# arduino_ir_receiver.net
KiCad netlist of a schematic drawn in EAGLE
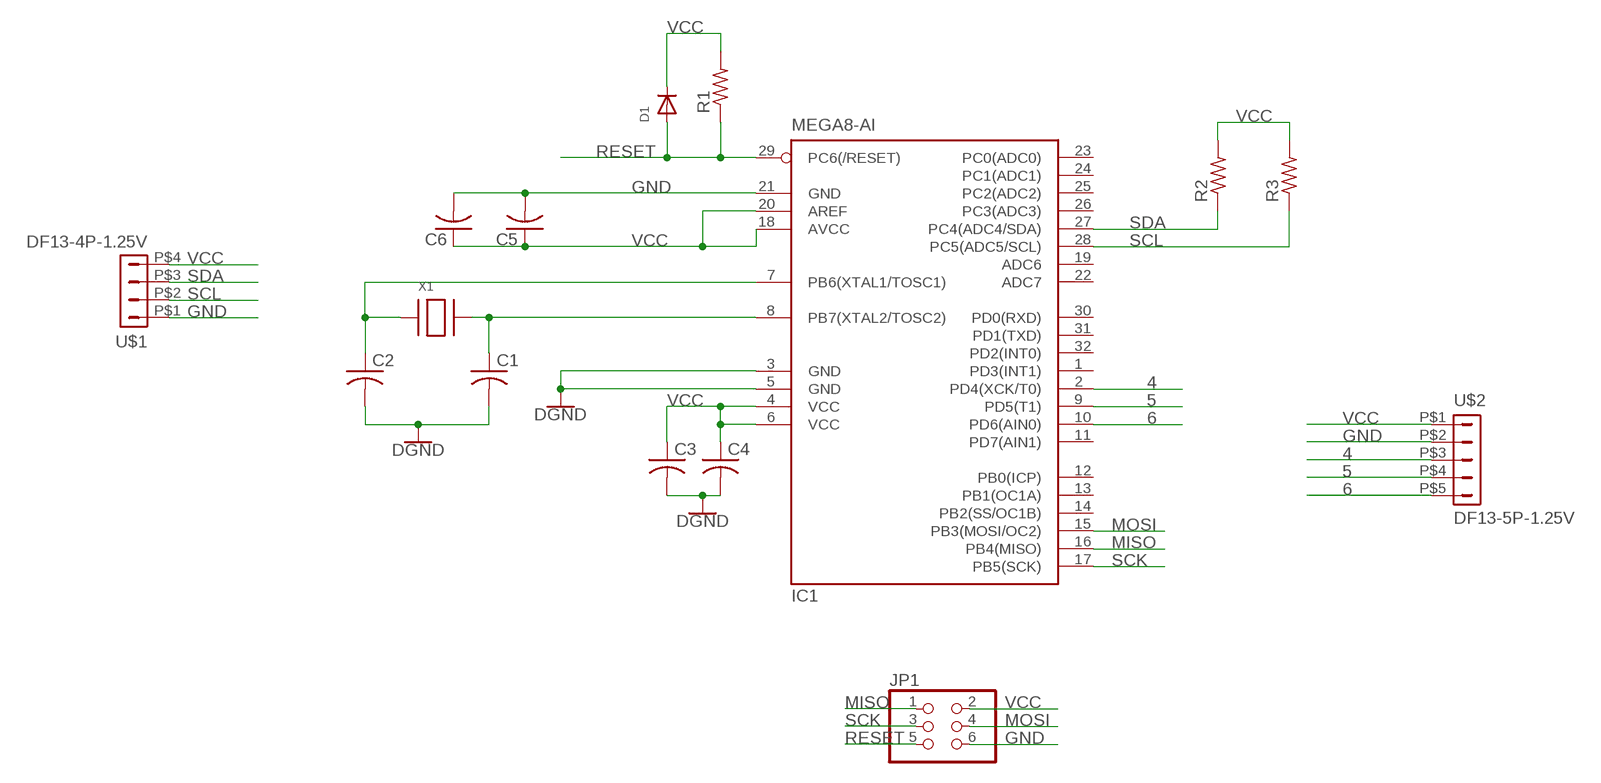
[diagram p0: schematic, sheet 1]

(export (version "E")
  (design (tool "Eeschema 10.0.6"))
  (components
    (comp (ref "C1")
      (value "C-USC0805")
      (footprint "eagle-import:C0805")
      (libsource (lib "eagle-import") (part "C-USC0805"))
    )
    (comp (ref "C2")
      (value "C-USC0805")
      (footprint "eagle-import:C0805")
      (libsource (lib "eagle-import") (part "C-USC0805"))
    )
    (comp (ref "C3")
      (value "C-USC0805")
      (footprint "eagle-import:C0805")
      (libsource (lib "eagle-import") (part "C-USC0805"))
    )
    (comp (ref "C4")
      (value "C-USC0805")
      (footprint "eagle-import:C0805")
      (libsource (lib "eagle-import") (part "C-USC0805"))
    )
    (comp (ref "C5")
      (value "C-USC0805")
      (footprint "eagle-import:C0805")
      (libsource (lib "eagle-import") (part "C-USC0805"))
    )
    (comp (ref "C6")
      (value "C-USC0805")
      (footprint "eagle-import:C0805")
      (libsource (lib "eagle-import") (part "C-USC0805"))
    )
    (comp (ref "D1")
      (value "DIODESOD-123")
      (footprint "eagle-import:SOD-123")
      (libsource (lib "eagle-import") (part "DIODESOD-123"))
    )
    (comp (ref "IC1")
      (value "MEGA8-AI")
      (footprint "eagle-import:TQFP32-08")
      (fields (field (name "MPN") "ATMEGA8-16AU"))
      (libsource (lib "eagle-import") (part "MEGA8-AI"))
    )
    (comp (ref "JP1")
      (value "PINHD-2X3")
      (footprint "eagle-import:2X03")
      (libsource (lib "eagle-import") (part "PINHD-2X3"))
    )
    (comp (ref "R1")
      (value "R-US_R0805")
      (footprint "eagle-import:R0805")
      (libsource (lib "eagle-import") (part "R-US_R0805"))
    )
    (comp (ref "R2")
      (value "R-US_R0805")
      (footprint "eagle-import:R0805")
      (libsource (lib "eagle-import") (part "R-US_R0805"))
    )
    (comp (ref "R3")
      (value "R-US_R0805")
      (footprint "eagle-import:R0805")
      (libsource (lib "eagle-import") (part "R-US_R0805"))
    )
    (comp (ref "U$1")
      (value "DF13-4P-1.25V")
      (footprint "eagle-import:DF13C-4P-1.25V")
      (libsource (lib "eagle-import") (part "DF13-4P-1.25V"))
    )
    (comp (ref "U$2")
      (value "DF13-5P-1.25V")
      (footprint "eagle-import:DF13C-5P-1.25V")
      (libsource (lib "eagle-import") (part "DF13-5P-1.25V"))
    )
    (comp (ref "X1")
      (value "XTALNX5032")
      (footprint "eagle-import:NX5032")
      (libsource (lib "eagle-import") (part "XTALNX5032"))
    )
  )
  (nets
    (net (code "1") (name "/4") (class "Default")
      (node (ref "IC1") (pin "2") (pinfunction "PD4(XCK/T0)_2") (pintype "bidirectional"))
      (node (ref "U$2") (pin "P$3") (pinfunction "3_P$3") (pintype "passive"))
    )
    (net (code "2") (name "/5") (class "Default")
      (node (ref "IC1") (pin "9") (pinfunction "PD5(T1)_9") (pintype "bidirectional"))
      (node (ref "U$2") (pin "P$4") (pinfunction "4_P$4") (pintype "passive"))
    )
    (net (code "3") (name "/6") (class "Default")
      (node (ref "IC1") (pin "10") (pinfunction "PD6(AIN0)_10") (pintype "bidirectional"))
      (node (ref "U$2") (pin "P$5") (pinfunction "5_P$5") (pintype "passive"))
    )
    (net (code "4") (name "/MISO") (class "Default")
      (node (ref "IC1") (pin "16") (pinfunction "PB4(MISO)_16") (pintype "bidirectional"))
      (node (ref "JP1") (pin "1") (pinfunction "1_1") (pintype "passive"))
    )
    (net (code "5") (name "/MOSI") (class "Default")
      (node (ref "IC1") (pin "15") (pinfunction "PB3(MOSI/OC2)_15") (pintype "bidirectional"))
      (node (ref "JP1") (pin "4") (pinfunction "4_4") (pintype "passive"))
    )
    (net (code "6") (name "/RESET") (class "Default")
      (node (ref "D1") (pin "A") (pinfunction "A_A") (pintype "passive"))
      (node (ref "IC1") (pin "29") (pinfunction "PC6(/RESET)_29") (pintype "bidirectional"))
      (node (ref "JP1") (pin "5") (pinfunction "5_5") (pintype "passive"))
      (node (ref "R1") (pin "1") (pinfunction "1_1") (pintype "passive"))
    )
    (net (code "7") (name "/SCK") (class "Default")
      (node (ref "IC1") (pin "17") (pinfunction "PB5(SCK)_17") (pintype "bidirectional"))
      (node (ref "JP1") (pin "3") (pinfunction "3_3") (pintype "passive"))
    )
    (net (code "8") (name "/SCL") (class "Default")
      (node (ref "IC1") (pin "28") (pinfunction "PC5(ADC5/SCL)_28") (pintype "bidirectional"))
      (node (ref "R3") (pin "1") (pinfunction "1_1") (pintype "passive"))
      (node (ref "U$1") (pin "P$2") (pinfunction "2_P$2") (pintype "passive"))
    )
    (net (code "9") (name "/SDA") (class "Default")
      (node (ref "IC1") (pin "27") (pinfunction "PC4(ADC4/SDA)_27") (pintype "bidirectional"))
      (node (ref "R2") (pin "1") (pinfunction "1_1") (pintype "passive"))
      (node (ref "U$1") (pin "P$3") (pinfunction "3_P$3") (pintype "passive"))
    )
    (net (code "10") (name "/VCC") (class "Default")
      (node (ref "C3") (pin "1") (pinfunction "1_1") (pintype "passive"))
      (node (ref "C4") (pin "1") (pinfunction "1_1") (pintype "passive"))
      (node (ref "C5") (pin "1") (pinfunction "1_1") (pintype "passive"))
      (node (ref "C6") (pin "1") (pinfunction "1_1") (pintype "passive"))
      (node (ref "D1") (pin "C") (pinfunction "C_C") (pintype "passive"))
      (node (ref "IC1") (pin "18") (pinfunction "AVCC_18") (pintype "power_in"))
      (node (ref "IC1") (pin "20") (pinfunction "AREF_20") (pintype "passive"))
      (node (ref "IC1") (pin "4") (pinfunction "VCC_4") (pintype "power_in"))
      (node (ref "IC1") (pin "6") (pinfunction "VCC_6") (pintype "power_in"))
      (node (ref "JP1") (pin "2") (pinfunction "2_2") (pintype "passive"))
      (node (ref "R1") (pin "2") (pinfunction "2_2") (pintype "passive"))
      (node (ref "R2") (pin "2") (pinfunction "2_2") (pintype "passive"))
      (node (ref "R3") (pin "2") (pinfunction "2_2") (pintype "passive"))
      (node (ref "U$1") (pin "P$4") (pinfunction "4_P$4") (pintype "passive"))
      (node (ref "U$2") (pin "P$1") (pinfunction "1_P$1") (pintype "passive"))
    )
    (net (code "11") (name "DGND") (class "Default")
      (node (ref "C1") (pin "2") (pinfunction "2_2") (pintype "passive"))
      (node (ref "C2") (pin "2") (pinfunction "2_2") (pintype "passive"))
      (node (ref "C3") (pin "2") (pinfunction "2_2") (pintype "passive"))
      (node (ref "C4") (pin "2") (pinfunction "2_2") (pintype "passive"))
      (node (ref "C5") (pin "2") (pinfunction "2_2") (pintype "passive"))
      (node (ref "C6") (pin "2") (pinfunction "2_2") (pintype "passive"))
      (node (ref "IC1") (pin "21") (pinfunction "GND_21") (pintype "power_in"))
      (node (ref "IC1") (pin "3") (pinfunction "GND_3") (pintype "power_in"))
      (node (ref "IC1") (pin "5") (pinfunction "GND_5") (pintype "power_in"))
      (node (ref "JP1") (pin "6") (pinfunction "6_6") (pintype "passive"))
      (node (ref "U$1") (pin "P$1") (pinfunction "1_P$1") (pintype "passive"))
      (node (ref "U$2") (pin "P$2") (pinfunction "2_P$2") (pintype "passive"))
    )
    (net (code "12") (name "Net-(IC1-PB6(XTAL1{slash}TOSC1))") (class "Default")
      (node (ref "C2") (pin "1") (pinfunction "1_1") (pintype "passive"))
      (node (ref "IC1") (pin "7") (pinfunction "PB6(XTAL1/TOSC1)_7") (pintype "bidirectional"))
      (node (ref "X1") (pin "P$1") (pinfunction "P$1_P$1") (pintype "bidirectional"))
    )
    (net (code "13") (name "Net-(IC1-PB7(XTAL2{slash}TOSC2))") (class "Default")
      (node (ref "C1") (pin "1") (pinfunction "1_1") (pintype "passive"))
      (node (ref "IC1") (pin "8") (pinfunction "PB7(XTAL2/TOSC2)_8") (pintype "bidirectional"))
      (node (ref "X1") (pin "P$2") (pinfunction "P$2_P$2") (pintype "bidirectional"))
    )
    (net (code "14") (name "unconnected-(IC1-ADC6-Pad19)") (class "Default")
      (node (ref "IC1") (pin "19") (pinfunction "ADC6_19") (pintype "bidirectional"))
    )
    (net (code "15") (name "unconnected-(IC1-ADC7-Pad22)") (class "Default")
      (node (ref "IC1") (pin "22") (pinfunction "ADC7_22") (pintype "bidirectional"))
    )
    (net (code "16") (name "unconnected-(IC1-PB0(ICP)-Pad12)") (class "Default")
      (node (ref "IC1") (pin "12") (pinfunction "PB0(ICP)_12") (pintype "bidirectional"))
    )
    (net (code "17") (name "unconnected-(IC1-PB1(OC1A)-Pad13)") (class "Default")
      (node (ref "IC1") (pin "13") (pinfunction "PB1(OC1A)_13") (pintype "bidirectional"))
    )
    (net (code "18") (name "unconnected-(IC1-PB2(SS{slash}OC1B)-Pad14)") (class "Default")
      (node (ref "IC1") (pin "14") (pinfunction "PB2(SS/OC1B)_14") (pintype "bidirectional"))
    )
    (net (code "19") (name "unconnected-(IC1-PC0(ADC0)-Pad23)") (class "Default")
      (node (ref "IC1") (pin "23") (pinfunction "PC0(ADC0)_23") (pintype "bidirectional"))
    )
    (net (code "20") (name "unconnected-(IC1-PC1(ADC1)-Pad24)") (class "Default")
      (node (ref "IC1") (pin "24") (pinfunction "PC1(ADC1)_24") (pintype "bidirectional"))
    )
    (net (code "21") (name "unconnected-(IC1-PC2(ADC2)-Pad25)") (class "Default")
      (node (ref "IC1") (pin "25") (pinfunction "PC2(ADC2)_25") (pintype "bidirectional"))
    )
    (net (code "22") (name "unconnected-(IC1-PC3(ADC3)-Pad26)") (class "Default")
      (node (ref "IC1") (pin "26") (pinfunction "PC3(ADC3)_26") (pintype "bidirectional"))
    )
    (net (code "23") (name "unconnected-(IC1-PD0(RXD)-Pad30)") (class "Default")
      (node (ref "IC1") (pin "30") (pinfunction "PD0(RXD)_30") (pintype "bidirectional"))
    )
    (net (code "24") (name "unconnected-(IC1-PD1(TXD)-Pad31)") (class "Default")
      (node (ref "IC1") (pin "31") (pinfunction "PD1(TXD)_31") (pintype "bidirectional"))
    )
    (net (code "25") (name "unconnected-(IC1-PD2(INT0)-Pad32)") (class "Default")
      (node (ref "IC1") (pin "32") (pinfunction "PD2(INT0)_32") (pintype "bidirectional"))
    )
    (net (code "26") (name "unconnected-(IC1-PD3(INT1)-Pad1)") (class "Default")
      (node (ref "IC1") (pin "1") (pinfunction "PD3(INT1)_1") (pintype "bidirectional"))
    )
    (net (code "27") (name "unconnected-(IC1-PD7(AIN1)-Pad11)") (class "Default")
      (node (ref "IC1") (pin "11") (pinfunction "PD7(AIN1)_11") (pintype "bidirectional"))
    )
  )
)
